# compare6_1.net
KiCad netlist of a schematic drawn in EAGLE
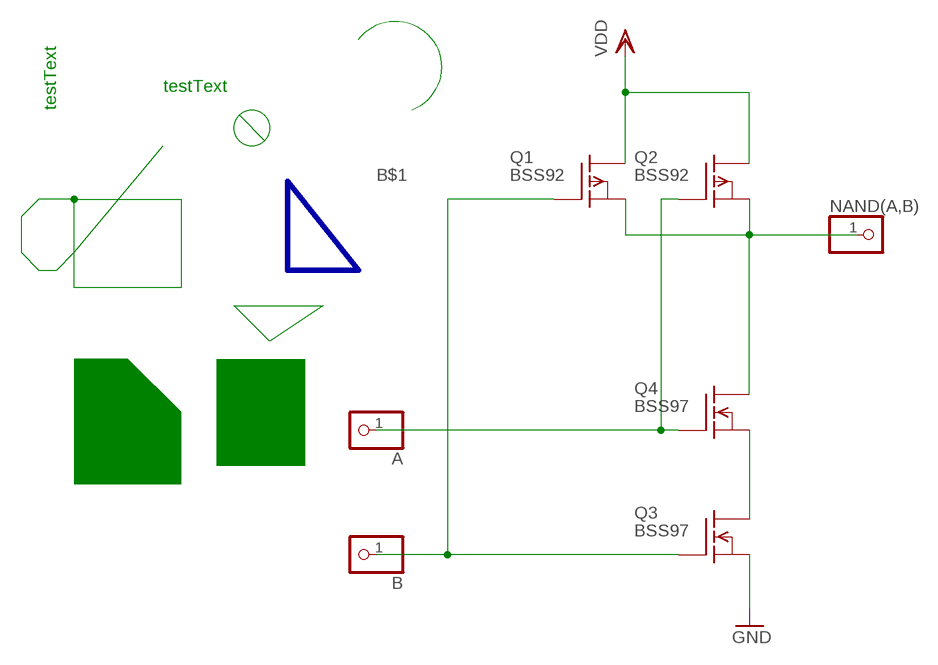
[diagram p0: schematic, sheet 1]

(export (version "E")
  (design (tool "Eeschema 10.0.6"))
  (components
    (comp (ref "A")
      (value "PINHD-1X1")
      (footprint "eagle-import:1X01")
      (libsource (lib "eagle-import") (part "PINHD-1X1"))
    )
    (comp (ref "B")
      (value "PINHD-1X1")
      (footprint "eagle-import:1X01")
      (libsource (lib "eagle-import") (part "PINHD-1X1"))
    )
    (comp (ref "NAND(A,B)")
      (value "PINHD-1X1")
      (footprint "eagle-import:1X01")
      (libsource (lib "eagle-import") (part "PINHD-1X1"))
    )
    (comp (ref "Q1")
      (value "BSS92")
      (footprint "eagle-import:TO92")
      (libsource (lib "eagle-import") (part "BSS92"))
    )
    (comp (ref "Q2")
      (value "BSS92")
      (footprint "eagle-import:TO92")
      (libsource (lib "eagle-import") (part "BSS92"))
    )
    (comp (ref "Q3")
      (value "BSS97")
      (footprint "eagle-import:TO202")
      (libsource (lib "eagle-import") (part "BSS97"))
    )
    (comp (ref "Q4")
      (value "BSS97")
      (footprint "eagle-import:TO202")
      (libsource (lib "eagle-import") (part "BSS97"))
    )
  )
  (nets
    (net (code "3") (name "GND") (class "Default")
      (node (ref "Q3") (pin "1") (pinfunction "S_1") (pintype "passive"))
    )
    (net (code "4") (name "Net-(Q1-G)") (class "Default")
      (node (ref "B") (pin "1") (pinfunction "1_1") (pintype "passive"))
      (node (ref "Q1") (pin "1") (pinfunction "G_1") (pintype "passive"))
      (node (ref "Q3") (pin "3") (pinfunction "G_3") (pintype "passive"))
    )
    (net (code "5") (name "Net-(Q1-S)") (class "Default")
      (node (ref "NAND(A,B)") (pin "1") (pinfunction "1_1") (pintype "passive"))
      (node (ref "Q1") (pin "3") (pinfunction "S_3") (pintype "passive"))
      (node (ref "Q2") (pin "3") (pinfunction "S_3") (pintype "passive"))
      (node (ref "Q4") (pin "2") (pinfunction "D_2") (pintype "passive"))
    )
    (net (code "6") (name "Net-(Q2-G)") (class "Default")
      (node (ref "A") (pin "1") (pinfunction "1_1") (pintype "passive"))
      (node (ref "Q2") (pin "1") (pinfunction "G_1") (pintype "passive"))
      (node (ref "Q4") (pin "3") (pinfunction "G_3") (pintype "passive"))
    )
    (net (code "7") (name "Net-(Q3-D)") (class "Default")
      (node (ref "Q3") (pin "2") (pinfunction "D_2") (pintype "passive"))
      (node (ref "Q4") (pin "1") (pinfunction "S_1") (pintype "passive"))
    )
    (net (code "8") (name "VDD") (class "Default")
      (node (ref "Q1") (pin "2") (pinfunction "D_2") (pintype "passive"))
      (node (ref "Q2") (pin "2") (pinfunction "D_2") (pintype "passive"))
    )
  )
)
